# LV1.net
KiCad netlist of a schematic drawn in Altium Designer
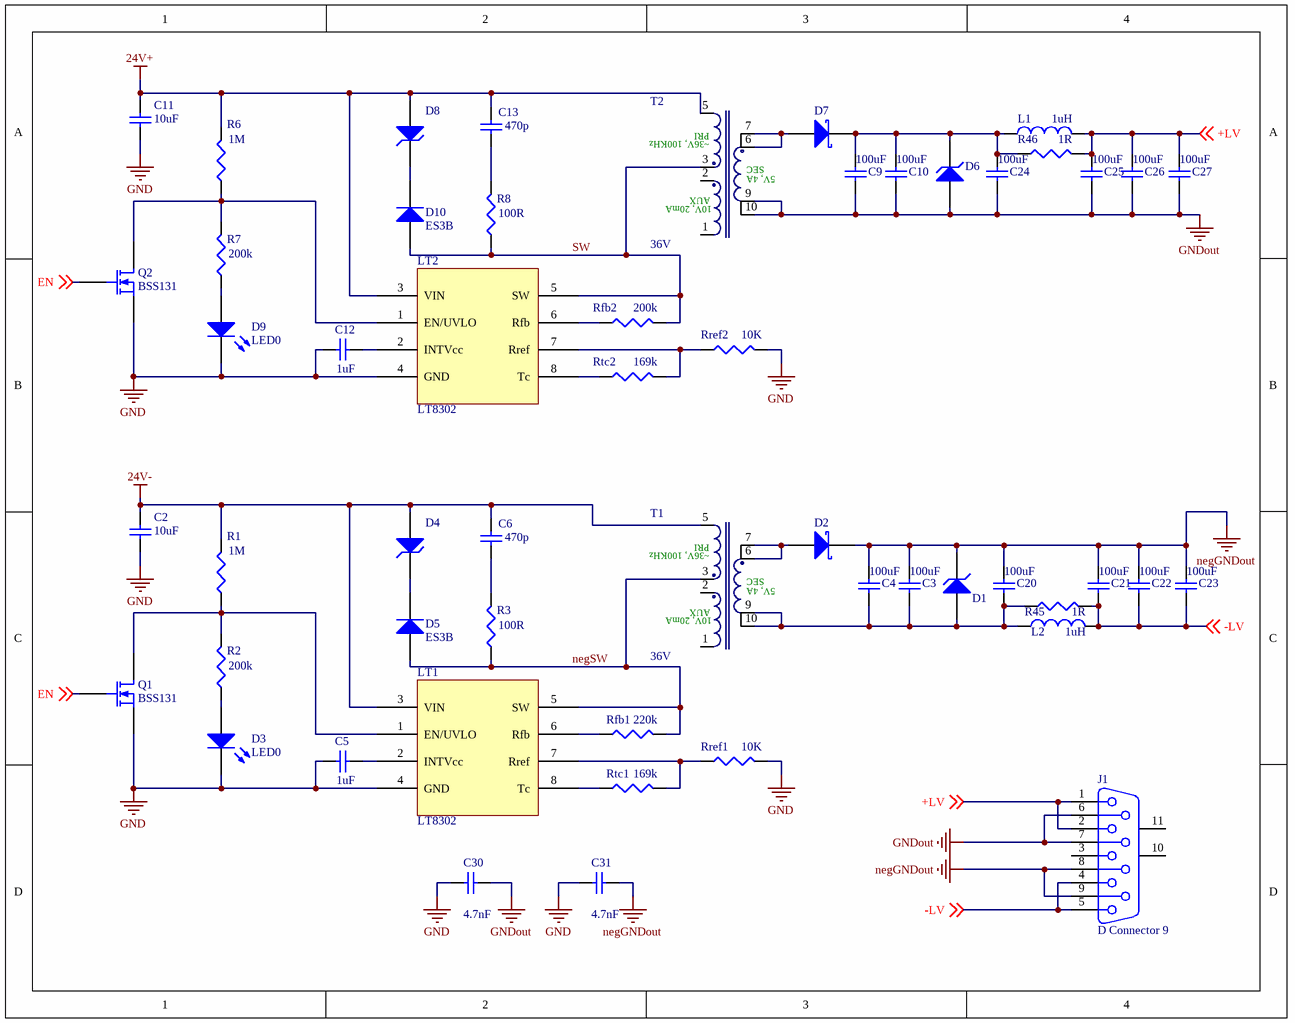
[diagram p0: LV1.schdoc]

(export (version "E")
  (design (tool "Eeschema 10.0.6"))
  (components
    (comp (ref "C2")
      (value "10uF")
      (footprint "C1210")
      (fields
        (field (name "PARTNO") "UMK325BJ106KM-T")
        (field (name "Comment") "Cap Semi")
        (field (name "PUBLISHER") "Altium Limited")
      )
      (libsource (lib "Miscellaneous Devices") (part "Cap Semi"))
    )
    (comp (ref "C3")
      (value "100uF")
      (footprint "C1210")
      (description "Capacitor (Semiconductor SIM Model)")
      (fields
        (field (name "PARTNO") "C3225X5R0J107M250AC")
        (field (name "Comment") "Cap Semi")
        (field (name "PUBLISHER") "Altium Limited")
      )
      (libsource (lib "Miscellaneous Devices") (part "Cap Semi"))
    )
    (comp (ref "C4")
      (value "100uF")
      (footprint "C1210")
      (description "Capacitor (Semiconductor SIM Model)")
      (fields
        (field (name "PARTNO") "C3225X5R0J107M250AC")
        (field (name "Comment") "Cap Semi")
        (field (name "PUBLISHER") "Altium Limited")
      )
      (libsource (lib "Miscellaneous Devices") (part "Cap Semi"))
    )
    (comp (ref "C5")
      (value "1uF")
      (footprint "1608[0603]")
      (description "Capacitor (Semiconductor SIM Model)")
      (fields
        (field (name "PARTNO") "06033D105KAT2A")
        (field (name "Comment") "Cap Semi")
        (field (name "PUBLISHER") "Altium Limited")
      )
      (libsource (lib "Miscellaneous Devices") (part "Cap Semi"))
    )
    (comp (ref "C6")
      (value "470p")
      (fields
        (field (name "PARTNO") "08055A221JAT2A")
        (field (name "Comment") "Cap Semi")
        (field (name "PUBLISHER") "Altium Limited")
      )
      (libsource (lib "Miscellaneous Devices") (part "Cap Semi"))
    )
    (comp (ref "C9")
      (value "100uF")
      (footprint "C1210")
      (description "Capacitor (Semiconductor SIM Model)")
      (fields
        (field (name "PARTNO") "C3225X5R0J107M250AC")
        (field (name "Comment") "Cap Semi")
        (field (name "PUBLISHER") "Altium Limited")
      )
      (libsource (lib "Miscellaneous Devices") (part "Cap Semi"))
    )
    (comp (ref "C10")
      (value "100uF")
      (footprint "C1210")
      (description "Capacitor (Semiconductor SIM Model)")
      (fields
        (field (name "PARTNO") "C3225X5R0J107M250AC")
        (field (name "Comment") "Cap Semi")
        (field (name "PUBLISHER") "Altium Limited")
      )
      (libsource (lib "Miscellaneous Devices") (part "Cap Semi"))
    )
    (comp (ref "C11")
      (value "10uF")
      (footprint "C1210")
      (description "Capacitor (Semiconductor SIM Model)")
      (fields
        (field (name "PARTNO") "UMK325BJ106KM-T")
        (field (name "Comment") "Cap Semi")
        (field (name "PUBLISHER") "Altium Limited")
      )
      (libsource (lib "Miscellaneous Devices") (part "Cap Semi"))
    )
    (comp (ref "C12")
      (value "1uF")
      (footprint "1608[0603]")
      (description "Capacitor (Semiconductor SIM Model)")
      (fields
        (field (name "PARTNO") "06033D105KAT2A")
        (field (name "Comment") "Cap Semi")
        (field (name "PUBLISHER") "Altium Limited")
      )
      (libsource (lib "Miscellaneous Devices") (part "Cap Semi"))
    )
    (comp (ref "C13")
      (value "470p")
      (description "Capacitor (Semiconductor SIM Model)")
      (fields
        (field (name "PARTNO") "08055A221JAT2A")
        (field (name "Comment") "Cap Semi")
        (field (name "PUBLISHER") "Altium Limited")
      )
      (libsource (lib "Miscellaneous Devices") (part "Cap Semi"))
    )
    (comp (ref "C20")
      (value "100uF")
      (footprint "C1210")
      (description "Capacitor (Semiconductor SIM Model)")
      (fields
        (field (name "PARTNO") "C3225X5R0J107M250AC")
        (field (name "Comment") "Cap Semi")
        (field (name "PUBLISHER") "Altium Limited")
      )
      (libsource (lib "Miscellaneous Devices") (part "Cap Semi"))
    )
    (comp (ref "C21")
      (value "100uF")
      (footprint "C1210")
      (description "Capacitor (Semiconductor SIM Model)")
      (fields
        (field (name "PARTNO") "CL32A107MPVNNNE")
        (field (name "Comment") "Cap Semi")
        (field (name "PUBLISHER") "Altium Limited")
      )
      (libsource (lib "Miscellaneous Devices") (part "Cap Semi"))
    )
    (comp (ref "C22")
      (value "100uF")
      (footprint "C1210")
      (description "Capacitor (Semiconductor SIM Model)")
      (fields
        (field (name "PARTNO") "CL32A107MPVNNNE")
        (field (name "Comment") "Cap Semi")
        (field (name "PUBLISHER") "Altium Limited")
      )
      (libsource (lib "Miscellaneous Devices") (part "Cap Semi"))
    )
    (comp (ref "C23")
      (value "100uF")
      (footprint "C1210")
      (description "Capacitor (Semiconductor SIM Model)")
      (fields
        (field (name "PARTNO") "CL32A107MPVNNNE")
        (field (name "Comment") "Cap Semi")
        (field (name "PUBLISHER") "Altium Limited")
      )
      (libsource (lib "Miscellaneous Devices") (part "Cap Semi"))
    )
    (comp (ref "C24")
      (value "100uF")
      (footprint "C1210")
      (description "Capacitor (Semiconductor SIM Model)")
      (fields
        (field (name "PARTNO") "C3225X5R0J107M250AC")
        (field (name "Comment") "Cap Semi")
        (field (name "PUBLISHER") "Altium Limited")
      )
      (libsource (lib "Miscellaneous Devices") (part "Cap Semi"))
    )
    (comp (ref "C25")
      (value "100uF")
      (footprint "C1210")
      (description "Capacitor (Semiconductor SIM Model)")
      (fields
        (field (name "PARTNO") "CL32A107MPVNNNE")
        (field (name "Comment") "Cap Semi")
        (field (name "PUBLISHER") "Altium Limited")
      )
      (libsource (lib "Miscellaneous Devices") (part "Cap Semi"))
    )
    (comp (ref "C26")
      (value "100uF")
      (footprint "C1210")
      (description "Capacitor (Semiconductor SIM Model)")
      (fields
        (field (name "PARTNO") "CL32A107MPVNNNE")
        (field (name "Comment") "Cap Semi")
        (field (name "PUBLISHER") "Altium Limited")
      )
      (libsource (lib "Miscellaneous Devices") (part "Cap Semi"))
    )
    (comp (ref "C27")
      (value "100uF")
      (footprint "C1210")
      (description "Capacitor (Semiconductor SIM Model)")
      (fields
        (field (name "PARTNO") "CL32A107MPVNNNE")
        (field (name "Comment") "Cap Semi")
        (field (name "PUBLISHER") "Altium Limited")
      )
      (libsource (lib "Miscellaneous Devices") (part "Cap Semi"))
    )
    (comp (ref "C30")
      (value "4.7nF")
      (footprint "1812")
      (description "Capacitor (Semiconductor SIM Model)")
      (fields
        (field (name "PARTNO") "C1812C472KDRACTU")
        (field (name "Comment") "Cap Semi")
        (field (name "PUBLISHER") "Altium Limited")
      )
      (libsource (lib "Miscellaneous Devices") (part "Cap Semi"))
    )
    (comp (ref "C31")
      (value "4.7nF")
      (footprint "1812")
      (description "Capacitor (Semiconductor SIM Model)")
      (fields
        (field (name "PARTNO") "C1812C472KDRACTU")
        (field (name "Comment") "Cap Semi")
        (field (name "PUBLISHER") "Altium Limited")
      )
      (libsource (lib "Miscellaneous Devices") (part "Cap Semi"))
    )
    (comp (ref "D1")
      (value "BZT52H-B5V6")
      (footprint "SOD123F")
      (description "Zener Diode")
      (fields (field (name "PUBLISHER") "Altium Limited"))
      (libsource (lib "G2_LV") (part "BZT52H-B5V6"))
    )
    (comp (ref "D2")
      (value "PDS1040L")
      (footprint "PDS1040L")
      (description "Schottky Diode")
      (fields (field (name "PARTNO") "PDS1040L-13") (field (name "PUBLISHER") "Altium Limited"))
      (libsource (lib "G2_LV") (part "PDS1040L"))
    )
    (comp (ref "D3")
      (value "LED0")
      (footprint "LED-0")
      (description "Typical INFRARED GaAs LED")
      (fields (field (name "PUBLISHER") "Altium Limited"))
      (libsource (lib "Miscellaneous Devices") (part "LED0"))
    )
    (comp (ref "D4")
      (value "SMAJ30A")
      (footprint "DO-214AC")
      (description "Zener Diode")
      (fields (field (name "PUBLISHER") "Altium Limited"))
      (libsource (lib "Miscellaneous Devices") (part "D Zener"))
    )
    (comp (ref "D5")
      (value "ES3B")
      (footprint "DO-214AB")
      (description "Power Diode")
      (fields (field (name "PUBLISHER") "Altium Limited"))
      (libsource (lib "G2_LV") (part "ES3B"))
    )
    (comp (ref "D6")
      (value "BZT52H-B5V6")
      (footprint "SOD123F")
      (description "Zener Diode")
      (fields (field (name "PUBLISHER") "Altium Limited"))
      (libsource (lib "G2_LV") (part "BZT52H-B5V6"))
    )
    (comp (ref "D7")
      (value "PDS1040L")
      (footprint "PDS1040L")
      (description "Schottky Diode")
      (fields (field (name "PARTNO") "PDS1040L-13") (field (name "PUBLISHER") "Altium Limited"))
      (libsource (lib "G2_LV") (part "PDS1040L"))
    )
    (comp (ref "D8")
      (value "SMAJ30A")
      (footprint "DO-214AC")
      (description "Zener Diode")
      (fields (field (name "PUBLISHER") "Altium Limited"))
      (libsource (lib "Miscellaneous Devices") (part "D Zener"))
    )
    (comp (ref "D9")
      (value "LED0")
      (footprint "LED-0")
      (description "Typical INFRARED GaAs LED")
      (fields (field (name "PUBLISHER") "Altium Limited"))
      (libsource (lib "Miscellaneous Devices") (part "LED0"))
    )
    (comp (ref "D10")
      (value "ES3B")
      (footprint "DO-214AB")
      (description "Power Diode")
      (fields (field (name "PUBLISHER") "Altium Limited"))
      (libsource (lib "G2_LV") (part "ES3B"))
    )
    (comp (ref "J1")
      (value "D Connector 9")
      (footprint "DSUB1.385-2H9")
      (description "Receptacle Assembly, 9 Position, Right Angle")
      (fields (field (name "PARTNO") "1734354-1") (field (name "PUBLISHER") "Altium Limited"))
      (libsource (lib "G2_LV") (part "D Connector 9"))
    )
    (comp (ref "L1")
      (value "1uH")
      (footprint "MPLC0730")
      (description "Inductor")
      (fields (field (name "PARTNO") "MPLC0730L1R0") (field (name "PUBLISHER") "Altium Limited"))
      (libsource (lib "G2_LV") (part "Inductor"))
    )
    (comp (ref "L2")
      (value "1uH")
      (footprint "MPLC0730")
      (description "Inductor")
      (fields (field (name "PARTNO") "MPLC0730L1R0") (field (name "PUBLISHER") "Altium Limited"))
      (libsource (lib "G2_LV") (part "Inductor"))
    )
    (comp (ref "LT1")
      (value "LT8302")
      (footprint "S8E")
      (fields (field (name "PARTNO") "LT8302ES8E#PBF"))
      (libsource (lib "G2_LV") (part "LT8302"))
    )
    (comp (ref "LT2")
      (value "LT8302")
      (footprint "S8E")
      (fields (field (name "PARTNO") "LT8302ES8E#PBF"))
      (libsource (lib "G2_LV") (part "LT8302"))
    )
    (comp (ref "Q1")
      (value "BSS131")
      (footprint "SOT-23")
      (description "N-Channel MOSFET")
      (fields (field (name "PUBLISHER") "Altium Limited"))
      (libsource (lib "G2_LV") (part "BSS131"))
    )
    (comp (ref "Q2")
      (value "BSS131")
      (footprint "SOT-23")
      (description "N-Channel MOSFET")
      (fields (field (name "PUBLISHER") "Altium Limited"))
      (libsource (lib "G2_LV") (part "BSS131"))
    )
    (comp (ref "R1")
      (value "1M")
      (footprint "J1-0603")
      (description "Resistor")
      (fields (field (name "Comment") "Res3") (field (name "PUBLISHER") "Altium Limited"))
      (libsource (lib "Miscellaneous Devices") (part "Res3"))
    )
    (comp (ref "R2")
      (value "200k")
      (footprint "J1-0603")
      (description "Resistor")
      (fields (field (name "Comment") "Res3") (field (name "PUBLISHER") "Altium Limited"))
      (libsource (lib "Miscellaneous Devices") (part "Res3"))
    )
    (comp (ref "R3")
      (value "100R")
      (description "Resistor")
      (fields (field (name "Comment") "Res3") (field (name "PUBLISHER") "Altium Limited"))
      (libsource (lib "Miscellaneous Devices") (part "Res3"))
    )
    (comp (ref "R6")
      (value "1M")
      (footprint "J1-0603")
      (description "Resistor")
      (fields (field (name "Comment") "Res3") (field (name "PUBLISHER") "Altium Limited"))
      (libsource (lib "Miscellaneous Devices") (part "Res3"))
    )
    (comp (ref "R7")
      (value "200k")
      (footprint "J1-0603")
      (description "Resistor")
      (fields (field (name "Comment") "Res3") (field (name "PUBLISHER") "Altium Limited"))
      (libsource (lib "Miscellaneous Devices") (part "Res3"))
    )
    (comp (ref "R8")
      (value "100R")
      (description "Resistor")
      (fields (field (name "Comment") "Res3") (field (name "PUBLISHER") "Altium Limited"))
      (libsource (lib "Miscellaneous Devices") (part "Res3"))
    )
    (comp (ref "R45")
      (value "1R")
      (footprint "J1-0603")
      (description "Resistor")
      (fields (field (name "Comment") "Res3") (field (name "PUBLISHER") "Altium Limited"))
      (libsource (lib "Miscellaneous Devices") (part "Res3"))
    )
    (comp (ref "R46")
      (value "1R")
      (footprint "J1-0603")
      (description "Resistor")
      (fields (field (name "Comment") "Res3") (field (name "PUBLISHER") "Altium Limited"))
      (libsource (lib "Miscellaneous Devices") (part "Res3"))
    )
    (comp (ref "Rfb1")
      (value "220k")
      (footprint "J1-0603")
      (description "Resistor")
      (fields (field (name "Comment") "Res3") (field (name "PUBLISHER") "Altium Limited"))
      (libsource (lib "Miscellaneous Devices") (part "Res3"))
    )
    (comp (ref "Rfb2")
      (value "200k")
      (footprint "J1-0603")
      (description "Resistor")
      (fields (field (name "Comment") "Res3") (field (name "PUBLISHER") "Altium Limited"))
      (libsource (lib "Miscellaneous Devices") (part "Res3"))
    )
    (comp (ref "Rref1")
      (value "10K")
      (footprint "J1-0603")
      (description "Resistor")
      (fields (field (name "Comment") "Res3") (field (name "PUBLISHER") "Altium Limited"))
      (libsource (lib "Miscellaneous Devices") (part "Res3"))
    )
    (comp (ref "Rref2")
      (value "10K")
      (footprint "J1-0603")
      (description "Resistor")
      (fields (field (name "Comment") "Res3") (field (name "PUBLISHER") "Altium Limited"))
      (libsource (lib "Miscellaneous Devices") (part "Res3"))
    )
    (comp (ref "Rtc1")
      (value "169k")
      (footprint "J1-0603")
      (description "Resistor")
      (fields (field (name "Comment") "Res3") (field (name "PUBLISHER") "Altium Limited"))
      (libsource (lib "Miscellaneous Devices") (part "Res3"))
    )
    (comp (ref "Rtc2")
      (value "169k")
      (footprint "J1-0603")
      (description "Resistor")
      (fields (field (name "Comment") "Res3") (field (name "PUBLISHER") "Altium Limited"))
      (libsource (lib "Miscellaneous Devices") (part "Res3"))
    )
    (comp (ref "T1")
      (value "36V")
      (footprint "EP13")
      (description "Flyback Transformer")
      (fields
        (field (name "PARTNO") "750311457")
        (field (name "MANUFACTURER") "Würth Elektronik eiSos GmbH")
        (field (name "CREATED BY") "Otto Christin")
      )
      (libsource (lib "WE-FB") (part "WE-FB, 750311457"))
    )
    (comp (ref "T2")
      (value "36V")
      (footprint "EP13")
      (description "Flyback Transformer suitable or LT3573/ LT3574/ LT3575/ LT3748 WE-FB, Ui=36V")
      (fields
        (field (name "PARTNO") "750311457")
        (field (name "MANUFACTURER") "Würth Elektronik eiSos GmbH")
        (field (name "CREATED BY") "Otto Christin")
      )
      (libsource (lib "WE-FB") (part "WE-FB, 750311457"))
    )
  )
  (nets
    (net (code "1") (name "+LV") (class "Default")
      (node (ref "C25") (pin "2") (pinfunction "2_2") (pintype "passive"))
      (node (ref "C26") (pin "2") (pinfunction "2_2") (pintype "passive"))
      (node (ref "C27") (pin "2") (pinfunction "2_2") (pintype "passive"))
      (node (ref "J1") (pin "1") (pinfunction "1_1") (pintype "passive"))
      (node (ref "J1") (pin "2") (pinfunction "2_2") (pintype "passive"))
      (node (ref "L1") (pin "2") (pinfunction "2_2") (pintype "passive"))
      (node (ref "R46") (pin "2") (pinfunction "2_2") (pintype "passive"))
    )
    (net (code "2") (name "-LV") (class "Default")
      (node (ref "C21") (pin "1") (pinfunction "1_1") (pintype "passive"))
      (node (ref "C22") (pin "1") (pinfunction "1_1") (pintype "passive"))
      (node (ref "C23") (pin "1") (pinfunction "1_1") (pintype "passive"))
      (node (ref "J1") (pin "4") (pinfunction "4_4") (pintype "passive"))
      (node (ref "J1") (pin "5") (pinfunction "5_5") (pintype "passive"))
      (node (ref "L2") (pin "2") (pinfunction "2_2") (pintype "passive"))
      (node (ref "R45") (pin "2") (pinfunction "2_2") (pintype "passive"))
    )
    (net (code "3") (name "/SW") (class "Default")
      (node (ref "D10") (pin "2") (pinfunction "A_2") (pintype "passive"))
      (node (ref "LT2") (pin "5") (pinfunction "SW_5") (pintype "passive"))
      (node (ref "R8") (pin "1") (pinfunction "1_1") (pintype "passive"))
      (node (ref "Rfb2") (pin "2") (pinfunction "2_2") (pintype "passive"))
      (node (ref "T2") (pin "3") (pinfunction "3_3") (pintype "passive"))
    )
    (net (code "4") (name "/negSW") (class "Default")
      (node (ref "D5") (pin "2") (pinfunction "A_2") (pintype "passive"))
      (node (ref "LT1") (pin "5") (pinfunction "SW_5") (pintype "passive"))
      (node (ref "R3") (pin "1") (pinfunction "1_1") (pintype "passive"))
      (node (ref "Rfb1") (pin "2") (pinfunction "2_2") (pintype "passive"))
      (node (ref "T1") (pin "3") (pinfunction "3_3") (pintype "passive"))
    )
    (net (code "5") (name "24V+") (class "Default")
      (node (ref "C11") (pin "2") (pinfunction "2_2") (pintype "passive"))
      (node (ref "C13") (pin "2") (pinfunction "2_2") (pintype "passive"))
      (node (ref "D8") (pin "1") (pinfunction "A_1") (pintype "passive"))
      (node (ref "LT2") (pin "3") (pinfunction "VIN_3") (pintype "passive"))
      (node (ref "R6") (pin "2") (pinfunction "2_2") (pintype "passive"))
      (node (ref "T2") (pin "5") (pinfunction "5_5") (pintype "passive"))
    )
    (net (code "6") (name "24V-") (class "Default")
      (node (ref "C2") (pin "2") (pinfunction "2_2") (pintype "passive"))
      (node (ref "C6") (pin "2") (pinfunction "2_2") (pintype "passive"))
      (node (ref "D4") (pin "1") (pinfunction "A_1") (pintype "passive"))
      (node (ref "LT1") (pin "3") (pinfunction "VIN_3") (pintype "passive"))
      (node (ref "R1") (pin "2") (pinfunction "2_2") (pintype "passive"))
      (node (ref "T1") (pin "5") (pinfunction "5_5") (pintype "passive"))
    )
    (net (code "7") (name "EN") (class "Default")
      (node (ref "Q1") (pin "1") (pinfunction "G_1") (pintype "passive"))
      (node (ref "Q2") (pin "1") (pinfunction "G_1") (pintype "passive"))
    )
    (net (code "8") (name "GND") (class "Default")
      (node (ref "C11") (pin "1") (pinfunction "1_1") (pintype "passive"))
      (node (ref "C12") (pin "2") (pinfunction "2_2") (pintype "passive"))
      (node (ref "C2") (pin "1") (pinfunction "1_1") (pintype "passive"))
      (node (ref "C30") (pin "1") (pinfunction "1_1") (pintype "passive"))
      (node (ref "C31") (pin "1") (pinfunction "1_1") (pintype "passive"))
      (node (ref "C5") (pin "2") (pinfunction "2_2") (pintype "passive"))
      (node (ref "D3") (pin "2") (pinfunction "K_2") (pintype "passive"))
      (node (ref "D9") (pin "2") (pinfunction "K_2") (pintype "passive"))
      (node (ref "LT1") (pin "4") (pinfunction "GND_4") (pintype "passive"))
      (node (ref "LT2") (pin "4") (pinfunction "GND_4") (pintype "passive"))
      (node (ref "Q1") (pin "2") (pinfunction "S_2") (pintype "passive"))
      (node (ref "Q2") (pin "2") (pinfunction "S_2") (pintype "passive"))
      (node (ref "Rref1") (pin "2") (pinfunction "2_2") (pintype "passive"))
      (node (ref "Rref2") (pin "2") (pinfunction "2_2") (pintype "passive"))
    )
    (net (code "9") (name "GNDout") (class "Default")
      (node (ref "C10") (pin "1") (pinfunction "1_1") (pintype "passive"))
      (node (ref "C24") (pin "1") (pinfunction "1_1") (pintype "passive"))
      (node (ref "C25") (pin "1") (pinfunction "1_1") (pintype "passive"))
      (node (ref "C26") (pin "1") (pinfunction "1_1") (pintype "passive"))
      (node (ref "C27") (pin "1") (pinfunction "1_1") (pintype "passive"))
      (node (ref "C30") (pin "2") (pinfunction "2_2") (pintype "passive"))
      (node (ref "C9") (pin "1") (pinfunction "1_1") (pintype "passive"))
      (node (ref "D6") (pin "1") (pinfunction "A_1") (pintype "passive"))
      (node (ref "J1") (pin "6") (pinfunction "6_6") (pintype "passive"))
      (node (ref "J1") (pin "7") (pinfunction "7_7") (pintype "passive"))
      (node (ref "T2") (pin "10") (pinfunction "10_10") (pintype "passive"))
      (node (ref "T2") (pin "9") (pinfunction "9_9") (pintype "passive"))
    )
    (net (code "10") (name "Net-(C6-Pad1)") (class "Default")
      (node (ref "C6") (pin "1") (pinfunction "1_1") (pintype "passive"))
      (node (ref "R3") (pin "2") (pinfunction "2_2") (pintype "passive"))
    )
    (net (code "11") (name "Net-(C13-Pad1)") (class "Default")
      (node (ref "C13") (pin "1") (pinfunction "1_1") (pintype "passive"))
      (node (ref "R8") (pin "2") (pinfunction "2_2") (pintype "passive"))
    )
    (net (code "12") (name "Net-(D1-A)") (class "Default")
      (node (ref "C20") (pin "1") (pinfunction "1_1") (pintype "passive"))
      (node (ref "C3") (pin "1") (pinfunction "1_1") (pintype "passive"))
      (node (ref "C4") (pin "1") (pinfunction "1_1") (pintype "passive"))
      (node (ref "D1") (pin "1") (pinfunction "A_1") (pintype "passive"))
      (node (ref "L2") (pin "1") (pinfunction "1_1") (pintype "passive"))
      (node (ref "R45") (pin "1") (pinfunction "1_1") (pintype "passive"))
      (node (ref "T1") (pin "10") (pinfunction "10_10") (pintype "passive"))
      (node (ref "T1") (pin "9") (pinfunction "9_9") (pintype "passive"))
    )
    (net (code "13") (name "Net-(D2-A)") (class "Default")
      (node (ref "D2") (pin "1") (pinfunction "A_1") (pintype "passive"))
      (node (ref "T1") (pin "6") (pinfunction "6_6") (pintype "passive"))
      (node (ref "T1") (pin "7") (pinfunction "7_7") (pintype "passive"))
    )
    (net (code "14") (name "Net-(D3-A)") (class "Default")
      (node (ref "D3") (pin "1") (pinfunction "A_1") (pintype "passive"))
      (node (ref "R2") (pin "1") (pinfunction "1_1") (pintype "passive"))
    )
    (net (code "15") (name "Net-(D4-K)") (class "Default")
      (node (ref "D4") (pin "2") (pinfunction "K_2") (pintype "passive"))
      (node (ref "D5") (pin "1") (pinfunction "K_1") (pintype "passive"))
    )
    (net (code "16") (name "Net-(D6-K)") (class "Default")
      (node (ref "C10") (pin "2") (pinfunction "2_2") (pintype "passive"))
      (node (ref "C24") (pin "2") (pinfunction "2_2") (pintype "passive"))
      (node (ref "C9") (pin "2") (pinfunction "2_2") (pintype "passive"))
      (node (ref "D6") (pin "2") (pinfunction "K_2") (pintype "passive"))
      (node (ref "D7") (pin "2") (pinfunction "K_2") (pintype "passive"))
      (node (ref "L1") (pin "1") (pinfunction "1_1") (pintype "passive"))
      (node (ref "R46") (pin "1") (pinfunction "1_1") (pintype "passive"))
    )
    (net (code "17") (name "Net-(D7-A)") (class "Default")
      (node (ref "D7") (pin "1") (pinfunction "A_1") (pintype "passive"))
      (node (ref "T2") (pin "6") (pinfunction "6_6") (pintype "passive"))
      (node (ref "T2") (pin "7") (pinfunction "7_7") (pintype "passive"))
    )
    (net (code "18") (name "Net-(D9-A)") (class "Default")
      (node (ref "D9") (pin "1") (pinfunction "A_1") (pintype "passive"))
      (node (ref "R7") (pin "1") (pinfunction "1_1") (pintype "passive"))
    )
    (net (code "19") (name "Net-(D10-K)") (class "Default")
      (node (ref "D10") (pin "1") (pinfunction "K_1") (pintype "passive"))
      (node (ref "D8") (pin "2") (pinfunction "K_2") (pintype "passive"))
    )
    (net (code "20") (name "Net-(LT1-EN{slash}UVLO)") (class "Default")
      (node (ref "LT1") (pin "1") (pinfunction "EN/UVLO_1") (pintype "passive"))
      (node (ref "Q1") (pin "3") (pinfunction "D_3") (pintype "passive"))
      (node (ref "R1") (pin "1") (pinfunction "1_1") (pintype "passive"))
      (node (ref "R2") (pin "2") (pinfunction "2_2") (pintype "passive"))
    )
    (net (code "21") (name "Net-(LT1-INTVcc)") (class "Default")
      (node (ref "C5") (pin "1") (pinfunction "1_1") (pintype "passive"))
      (node (ref "LT1") (pin "2") (pinfunction "INTVcc_2") (pintype "passive"))
    )
    (net (code "22") (name "Net-(LT1-Rfb)") (class "Default")
      (node (ref "LT1") (pin "6") (pinfunction "Rfb_6") (pintype "passive"))
      (node (ref "Rfb1") (pin "1") (pinfunction "1_1") (pintype "passive"))
    )
    (net (code "23") (name "Net-(LT1-Rref)") (class "Default")
      (node (ref "LT1") (pin "7") (pinfunction "Rref_7") (pintype "passive"))
      (node (ref "Rref1") (pin "1") (pinfunction "1_1") (pintype "passive"))
      (node (ref "Rtc1") (pin "2") (pinfunction "2_2") (pintype "passive"))
    )
    (net (code "24") (name "Net-(LT1-Tc)") (class "Default")
      (node (ref "LT1") (pin "8") (pinfunction "Tc_8") (pintype "passive"))
      (node (ref "Rtc1") (pin "1") (pinfunction "1_1") (pintype "passive"))
    )
    (net (code "25") (name "Net-(LT2-EN{slash}UVLO)") (class "Default")
      (node (ref "LT2") (pin "1") (pinfunction "EN/UVLO_1") (pintype "passive"))
      (node (ref "Q2") (pin "3") (pinfunction "D_3") (pintype "passive"))
      (node (ref "R6") (pin "1") (pinfunction "1_1") (pintype "passive"))
      (node (ref "R7") (pin "2") (pinfunction "2_2") (pintype "passive"))
    )
    (net (code "26") (name "Net-(LT2-INTVcc)") (class "Default")
      (node (ref "C12") (pin "1") (pinfunction "1_1") (pintype "passive"))
      (node (ref "LT2") (pin "2") (pinfunction "INTVcc_2") (pintype "passive"))
    )
    (net (code "27") (name "Net-(LT2-Rfb)") (class "Default")
      (node (ref "LT2") (pin "6") (pinfunction "Rfb_6") (pintype "passive"))
      (node (ref "Rfb2") (pin "1") (pinfunction "1_1") (pintype "passive"))
    )
    (net (code "28") (name "Net-(LT2-Rref)") (class "Default")
      (node (ref "LT2") (pin "7") (pinfunction "Rref_7") (pintype "passive"))
      (node (ref "Rref2") (pin "1") (pinfunction "1_1") (pintype "passive"))
      (node (ref "Rtc2") (pin "2") (pinfunction "2_2") (pintype "passive"))
    )
    (net (code "29") (name "Net-(LT2-Tc)") (class "Default")
      (node (ref "LT2") (pin "8") (pinfunction "Tc_8") (pintype "passive"))
      (node (ref "Rtc2") (pin "1") (pinfunction "1_1") (pintype "passive"))
    )
    (net (code "30") (name "negGNDout") (class "Default")
      (node (ref "C20") (pin "2") (pinfunction "2_2") (pintype "passive"))
      (node (ref "C21") (pin "2") (pinfunction "2_2") (pintype "passive"))
      (node (ref "C22") (pin "2") (pinfunction "2_2") (pintype "passive"))
      (node (ref "C23") (pin "2") (pinfunction "2_2") (pintype "passive"))
      (node (ref "C3") (pin "2") (pinfunction "2_2") (pintype "passive"))
      (node (ref "C31") (pin "2") (pinfunction "2_2") (pintype "passive"))
      (node (ref "C4") (pin "2") (pinfunction "2_2") (pintype "passive"))
      (node (ref "D1") (pin "2") (pinfunction "K_2") (pintype "passive"))
      (node (ref "D2") (pin "2") (pinfunction "K_2") (pintype "passive"))
      (node (ref "J1") (pin "8") (pinfunction "8_8") (pintype "passive"))
      (node (ref "J1") (pin "9") (pinfunction "9_9") (pintype "passive"))
    )
    (net (code "31") (name "unconnected-(J1-MH1-Pad10)") (class "Default")
      (node (ref "J1") (pin "10") (pinfunction "MH1_10") (pintype "passive"))
    )
    (net (code "32") (name "unconnected-(J1-MH2-Pad11)") (class "Default")
      (node (ref "J1") (pin "11") (pinfunction "MH2_11") (pintype "passive"))
    )
    (net (code "33") (name "unconnected-(J1-Pad3)") (class "Default")
      (node (ref "J1") (pin "3") (pinfunction "3_3") (pintype "passive"))
    )
    (net (code "34") (name "unconnected-(T1-Pad1)") (class "Default")
      (node (ref "T1") (pin "1") (pinfunction "1_1") (pintype "passive"))
    )
    (net (code "35") (name "unconnected-(T1-Pad2)") (class "Default")
      (node (ref "T1") (pin "2") (pinfunction "2_2") (pintype "passive"))
    )
    (net (code "36") (name "unconnected-(T2-Pad1)") (class "Default")
      (node (ref "T2") (pin "1") (pinfunction "1_1") (pintype "passive"))
    )
    (net (code "37") (name "unconnected-(T2-Pad2)") (class "Default")
      (node (ref "T2") (pin "2") (pinfunction "2_2") (pintype "passive"))
    )
  )
)
